# Sensors.net
KiCad netlist of a schematic drawn in Altium Designer
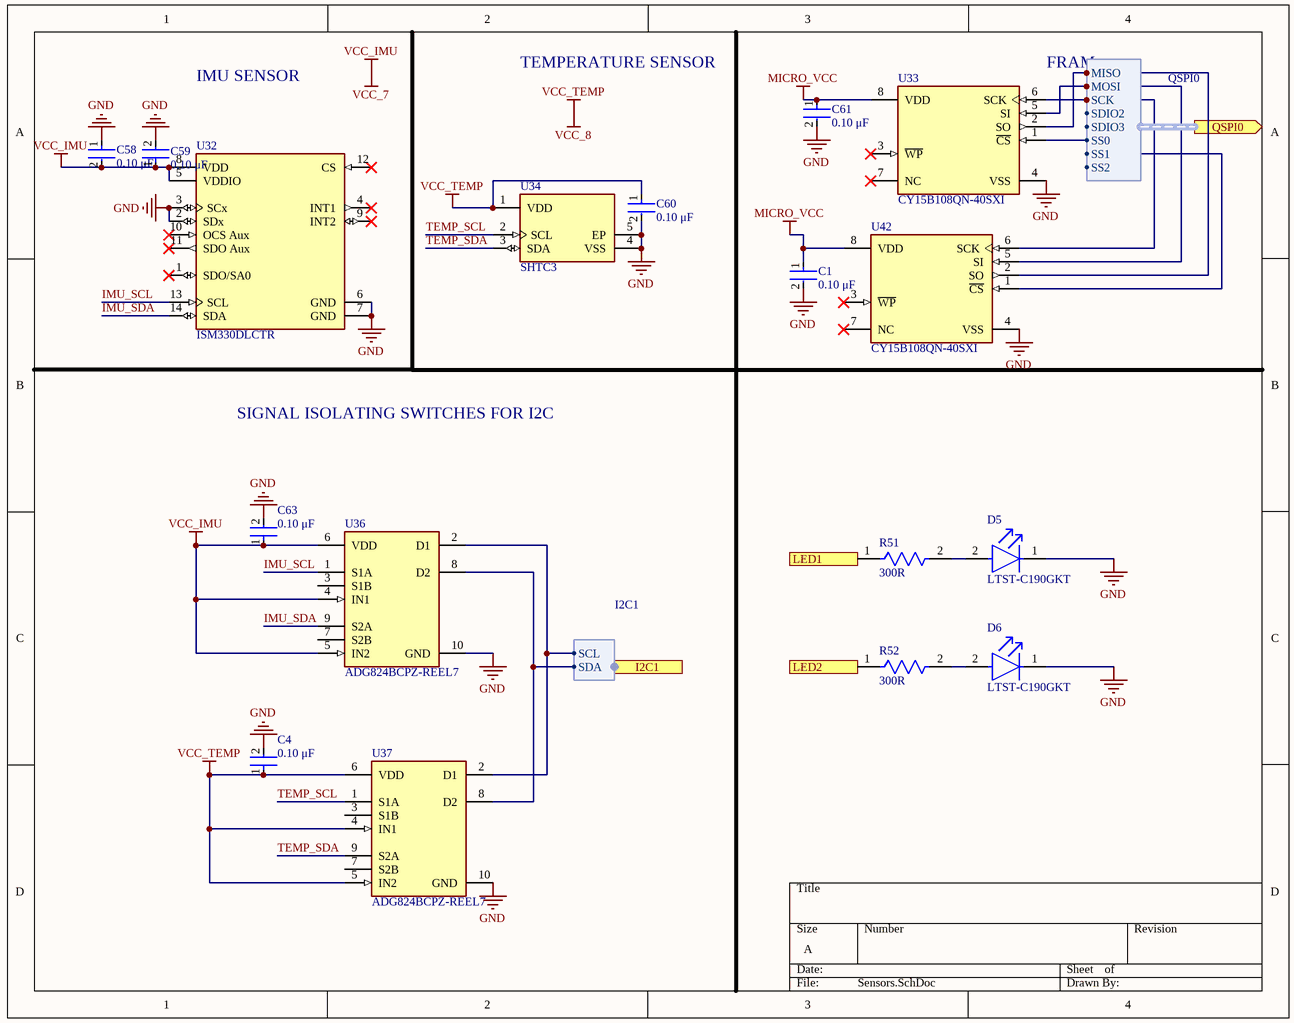
[diagram p0: Sensors.SchDoc]

(export (version "E")
  (design (tool "Eeschema 10.0.6"))
  (components
    (comp (ref "C1")
      (value "C0402C104K8PACTU")
      (footprint "FP-C0402-BB-MFG")
      (description "CAP CER 0.1UF 10V X5R 0402")
      (fields
        (field (name "CAPACITANCE") "0.10 μF")
        (field (name "MANUFACTURER") "Kemet")
        (field (name "TOLERANCE") "0.1")
      )
      (libsource (lib "Altium Content Vault") (part "b4654b650e69147ec39a6b967a45e02"))
    )
    (comp (ref "C4")
      (value "C0402C104K8PACTU")
      (footprint "FP-C0402-BB-MFG")
      (description "CAP CER 0.1UF 10V X5R 0402")
      (fields
        (field (name "CAPACITANCE") "0.10 μF")
        (field (name "MANUFACTURER") "Kemet")
        (field (name "TOLERANCE") "0.1")
      )
      (libsource (lib "Altium Content Vault") (part "b4654b650e69147ec39a6b967a45e02"))
    )
    (comp (ref "C58")
      (value "C0402C104K8PACTU")
      (footprint "FP-C0402-BB-MFG")
      (description "CAP CER 0.1UF 10V X5R 0402")
      (fields
        (field (name "CAPACITANCE") "0.10 μF")
        (field (name "MANUFACTURER") "Kemet")
        (field (name "TOLERANCE") "0.1")
      )
      (libsource (lib "Altium Content Vault") (part "b4654b650e69147ec39a6b967a45e02"))
    )
    (comp (ref "C59")
      (value "C0402C104K8PACTU")
      (footprint "FP-C0402-BB-MFG")
      (description "CAP CER 0.1UF 10V X5R 0402")
      (fields
        (field (name "CAPACITANCE") "0.10 μF")
        (field (name "MANUFACTURER") "Kemet")
        (field (name "TOLERANCE") "0.1")
      )
      (libsource (lib "Altium Content Vault") (part "b4654b650e69147ec39a6b967a45e02"))
    )
    (comp (ref "C60")
      (value "C0402C104K8PACTU")
      (footprint "FP-C0402-BB-MFG")
      (description "CAP CER 0.1UF 10V X5R 0402")
      (fields
        (field (name "CAPACITANCE") "0.10 μF")
        (field (name "MANUFACTURER") "Kemet")
        (field (name "TOLERANCE") "0.1")
      )
      (libsource (lib "Altium Content Vault") (part "b4654b650e69147ec39a6b967a45e02"))
    )
    (comp (ref "C61")
      (value "C0402C104K8PACTU")
      (footprint "FP-C0402-BB-MFG")
      (description "CAP CER 0.1UF 10V X5R 0402")
      (fields
        (field (name "CAPACITANCE") "0.10 μF")
        (field (name "MANUFACTURER") "Kemet")
        (field (name "TOLERANCE") "0.1")
      )
      (libsource (lib "Altium Content Vault") (part "b4654b650e69147ec39a6b967a45e02"))
    )
    (comp (ref "C63")
      (value "C0402C104K8PACTU")
      (footprint "FP-C0402-BB-MFG")
      (description "CAP CER 0.1UF 10V X5R 0402")
      (fields
        (field (name "CAPACITANCE") "0.10 μF")
        (field (name "MANUFACTURER") "Kemet")
        (field (name "TOLERANCE") "0.1")
      )
      (libsource (lib "Altium Content Vault") (part "b4654b650e69147ec39a6b967a45e02"))
    )
    (comp (ref "D5")
      (value "LTST-C190GKT")
      (footprint "FP-LTST-C190GKT-MFG")
      (description "LED GREEN CLEAR CHIP SMD")
      (fields (field (name "VOLTAGE") "2V"))
      (libsource (lib "Altium Content Vault") (part "8706943c75ba83719d021d2fdc84c58"))
    )
    (comp (ref "D6")
      (value "LTST-C190GKT")
      (footprint "FP-LTST-C190GKT-MFG")
      (description "LED GREEN CLEAR CHIP SMD")
      (fields (field (name "VOLTAGE") "2V"))
      (libsource (lib "Altium Content Vault") (part "8706943c75ba83719d021d2fdc84c58"))
    )
    (comp (ref "R51")
      (value "CRCW0603300RFKEA")
      (footprint "FP-CRCW0603-e3-IPC_A")
      (description "RES Thick Film, 300Ω, 1%, 0.1W, 100ppm/°C, 0603")
      (fields (field (name "TOLERANCE") "1%") (field (name "RESISTANCE") "300R"))
      (libsource (lib "Altium Content Vault") (part "1029c3af85768c4190bb7ad29bc67b5"))
    )
    (comp (ref "R52")
      (value "CRCW0603300RFKEA")
      (footprint "FP-CRCW0603-e3-IPC_A")
      (description "RES Thick Film, 300Ω, 1%, 0.1W, 100ppm/°C, 0603")
      (fields (field (name "TOLERANCE") "1%") (field (name "RESISTANCE") "300R"))
      (libsource (lib "Altium Content Vault") (part "1029c3af85768c4190bb7ad29bc67b5"))
    )
    (comp (ref "U32")
      (value "ISM330DLCTR")
      (footprint "FP-LGA-14L-DM00249496-MFG")
      (description "INEMO INERTIAL MODULE")
      (fields
        (field (name "MANUFACTURER") "STMicroelectronics")
        (field (name "OCTOPART") "https://octopart.com/ism330dlctr-stmicroelectronics-85149243")
      )
      (libsource (lib "Altium Content Vault") (part "7cb83b91da826bd22f6a735c633f5ac"))
    )
    (comp (ref "U33")
      (value "CY15B108QN-40SXI")
      (footprint "FP-001-85261-IPC_C")
      (description "IC FRAM 8MBIT 40MHZ 8EIAJ")
      (libsource (lib "Altium Content Vault") (part "94cc5f17500dd1907c0ebdcd3efa3d4"))
    )
    (comp (ref "U34")
      (value "SHTC3")
      (footprint "FP-SHTC3-MFG")
      (description "SENSOR HUMI/TEMP I2C 2% SMD")
      (fields
        (field (name "MANUFACTURER") "Sensirion")
        (field (name "OCTOPART") "https://octopart.com/shtc3-sensirion-91912225")
      )
      (libsource (lib "Altium Content Vault") (part "92e21da4ceb1e434b50171ab113565b"))
    )
    (comp (ref "U36")
      (value "ADG824BCPZ-REEL7")
      (footprint "FP-CP-10-10-MFG")
      (description "IC SWITCH DUAL SPDT 10LFCSP")
      (fields
        (field (name "OCTOPART") "https://octopart.com/adg824bcpz-reel7-analog+devices-12410880")
        (field (name "MANUFACTURER") "Analog Devices")
      )
      (libsource (lib "Altium Content Vault") (part "750f7653eda72c1ba3820f182f788e1"))
    )
    (comp (ref "U37")
      (value "ADG824BCPZ-REEL7")
      (footprint "FP-CP-10-10-MFG")
      (description "IC SWITCH DUAL SPDT 10LFCSP")
      (fields
        (field (name "OCTOPART") "https://octopart.com/adg824bcpz-reel7-analog+devices-12410880")
        (field (name "MANUFACTURER") "Analog Devices")
      )
      (libsource (lib "Altium Content Vault") (part "750f7653eda72c1ba3820f182f788e1"))
    )
    (comp (ref "U42")
      (value "CY15B108QN-40SXI")
      (footprint "FP-001-85261-IPC_C")
      (description "IC FRAM 8MBIT 40MHZ 8EIAJ")
      (libsource (lib "Altium Content Vault") (part "94cc5f17500dd1907c0ebdcd3efa3d4"))
    )
  )
  (nets
    (net (code "3") (name "/IMU_SCL") (class "Default")
      (node (ref "U32") (pin "13") (pinfunction "SCL_13") (pintype "input"))
      (node (ref "U36") (pin "1") (pinfunction "S1A_1") (pintype "passive"))
    )
    (net (code "4") (name "/IMU_SDA") (class "Default")
      (node (ref "U32") (pin "14") (pinfunction "SDA_14") (pintype "bidirectional"))
      (node (ref "U36") (pin "9") (pinfunction "S2A_9") (pintype "passive"))
    )
    (net (code "5") (name "/LED1") (class "Default")
      (node (ref "R51") (pin "1") (pinfunction "1_1") (pintype "passive"))
    )
    (net (code "6") (name "/LED2") (class "Default")
      (node (ref "R52") (pin "1") (pinfunction "1_1") (pintype "passive"))
    )
    (net (code "7") (name "/MISO") (class "Default")
      (node (ref "U33") (pin "2") (pinfunction "SO_2") (pintype "output"))
      (node (ref "U42") (pin "2") (pinfunction "SO_2") (pintype "output"))
    )
    (net (code "8") (name "/MOSI") (class "Default")
      (node (ref "U33") (pin "5") (pinfunction "SI_5") (pintype "input"))
      (node (ref "U42") (pin "5") (pinfunction "SI_5") (pintype "input"))
    )
    (net (code "9") (name "/SCK") (class "Default")
      (node (ref "U33") (pin "6") (pinfunction "SCK_6") (pintype "input"))
      (node (ref "U42") (pin "6") (pinfunction "SCK_6") (pintype "input"))
    )
    (net (code "10") (name "/SCL") (class "Default")
      (node (ref "U36") (pin "2") (pinfunction "D1_2") (pintype "passive"))
      (node (ref "U37") (pin "2") (pinfunction "D1_2") (pintype "passive"))
    )
    (net (code "11") (name "/SDA") (class "Default")
      (node (ref "U36") (pin "8") (pinfunction "D2_8") (pintype "passive"))
      (node (ref "U37") (pin "8") (pinfunction "D2_8") (pintype "passive"))
    )
    (net (code "12") (name "/SS0") (class "Default")
      (node (ref "U33") (pin "1") (pinfunction "~{CS}_1") (pintype "input"))
    )
    (net (code "13") (name "/SS1") (class "Default")
      (node (ref "U42") (pin "1") (pinfunction "~{CS}_1") (pintype "input"))
    )
    (net (code "14") (name "/TEMP_SCL") (class "Default")
      (node (ref "U34") (pin "2") (pinfunction "SCL_2") (pintype "input"))
      (node (ref "U37") (pin "1") (pinfunction "S1A_1") (pintype "passive"))
    )
    (net (code "15") (name "/TEMP_SDA") (class "Default")
      (node (ref "U34") (pin "3") (pinfunction "SDA_3") (pintype "bidirectional"))
      (node (ref "U37") (pin "9") (pinfunction "S2A_9") (pintype "passive"))
    )
    (net (code "18") (name "GND") (class "Default")
      (node (ref "C1") (pin "2") (pinfunction "2_2") (pintype "passive"))
      (node (ref "C4") (pin "2") (pinfunction "2_2") (pintype "passive"))
      (node (ref "C58") (pin "1") (pinfunction "1_1") (pintype "passive"))
      (node (ref "C59") (pin "2") (pinfunction "2_2") (pintype "passive"))
      (node (ref "C60") (pin "2") (pinfunction "2_2") (pintype "passive"))
      (node (ref "C61") (pin "2") (pinfunction "2_2") (pintype "passive"))
      (node (ref "C63") (pin "2") (pinfunction "2_2") (pintype "passive"))
      (node (ref "D5") (pin "1") (pinfunction "C_1") (pintype "passive"))
      (node (ref "D6") (pin "1") (pinfunction "C_1") (pintype "passive"))
      (node (ref "U32") (pin "2") (pinfunction "SDx_2") (pintype "bidirectional"))
      (node (ref "U32") (pin "3") (pinfunction "SCx_3") (pintype "bidirectional"))
      (node (ref "U32") (pin "6") (pinfunction "GND_6") (pintype "power_in"))
      (node (ref "U32") (pin "7") (pinfunction "GND_7") (pintype "power_in"))
      (node (ref "U33") (pin "4") (pinfunction "VSS_4") (pintype "power_in"))
      (node (ref "U34") (pin "4") (pinfunction "VSS_4") (pintype "power_in"))
      (node (ref "U34") (pin "5") (pinfunction "EP_5") (pintype "power_in"))
      (node (ref "U36") (pin "10") (pinfunction "GND_10") (pintype "power_in"))
      (node (ref "U37") (pin "10") (pinfunction "GND_10") (pintype "power_in"))
      (node (ref "U42") (pin "4") (pinfunction "VSS_4") (pintype "power_in"))
    )
    (net (code "19") (name "MICRO_VCC") (class "Default")
      (node (ref "C1") (pin "1") (pinfunction "1_1") (pintype "passive"))
      (node (ref "C61") (pin "1") (pinfunction "1_1") (pintype "passive"))
      (node (ref "U33") (pin "8") (pinfunction "VDD_8") (pintype "power_in"))
      (node (ref "U42") (pin "8") (pinfunction "VDD_8") (pintype "power_in"))
    )
    (net (code "20") (name "Net-(D5-A)") (class "Default")
      (node (ref "D5") (pin "2") (pinfunction "A_2") (pintype "passive"))
      (node (ref "R51") (pin "2") (pinfunction "2_2") (pintype "passive"))
    )
    (net (code "21") (name "Net-(D6-A)") (class "Default")
      (node (ref "D6") (pin "2") (pinfunction "A_2") (pintype "passive"))
      (node (ref "R52") (pin "2") (pinfunction "2_2") (pintype "passive"))
    )
    (net (code "22") (name "VCC_7") (class "Default")
      (node (ref "C58") (pin "2") (pinfunction "2_2") (pintype "passive"))
      (node (ref "C59") (pin "1") (pinfunction "1_1") (pintype "passive"))
      (node (ref "C63") (pin "1") (pinfunction "1_1") (pintype "passive"))
      (node (ref "U32") (pin "5") (pinfunction "VDDIO_5") (pintype "power_in"))
      (node (ref "U32") (pin "8") (pinfunction "VDD_8") (pintype "power_in"))
      (node (ref "U36") (pin "4") (pinfunction "IN1_4") (pintype "input"))
      (node (ref "U36") (pin "5") (pinfunction "IN2_5") (pintype "input"))
      (node (ref "U36") (pin "6") (pinfunction "VDD_6") (pintype "power_in"))
    )
    (net (code "23") (name "VCC_8") (class "Default")
      (node (ref "C4") (pin "1") (pinfunction "1_1") (pintype "passive"))
      (node (ref "C60") (pin "1") (pinfunction "1_1") (pintype "passive"))
      (node (ref "U34") (pin "1") (pinfunction "VDD_1") (pintype "power_in"))
      (node (ref "U37") (pin "4") (pinfunction "IN1_4") (pintype "input"))
      (node (ref "U37") (pin "5") (pinfunction "IN2_5") (pintype "input"))
      (node (ref "U37") (pin "6") (pinfunction "VDD_6") (pintype "power_in"))
    )
    (net (code "24") (name "unconnected-(U32-CS-Pad12)") (class "Default")
      (node (ref "U32") (pin "12") (pinfunction "CS_12") (pintype "input+no_connect"))
    )
    (net (code "25") (name "unconnected-(U32-INT1-Pad4)") (class "Default")
      (node (ref "U32") (pin "4") (pinfunction "INT1_4") (pintype "output+no_connect"))
    )
    (net (code "26") (name "unconnected-(U32-INT2-Pad9)") (class "Default")
      (node (ref "U32") (pin "9") (pinfunction "INT2_9") (pintype "bidirectional+no_connect"))
    )
    (net (code "27") (name "unconnected-(U32-OCS_Aux-Pad10)") (class "Default")
      (node (ref "U32") (pin "10") (pinfunction "OCS_Aux_10") (pintype "input+no_connect"))
    )
    (net (code "28") (name "unconnected-(U32-SDO_Aux-Pad11)") (class "Default")
      (node (ref "U32") (pin "11") (pinfunction "SDO_Aux_11") (pintype "output+no_connect"))
    )
    (net (code "29") (name "unconnected-(U32-SDO{slash}SA0-Pad1)") (class "Default")
      (node (ref "U32") (pin "1") (pinfunction "SDO/SA0_1") (pintype "bidirectional+no_connect"))
    )
    (net (code "30") (name "unconnected-(U33-NC-Pad7)") (class "Default")
      (node (ref "U33") (pin "7") (pinfunction "NC_7") (pintype "passive+no_connect"))
    )
    (net (code "31") (name "unconnected-(U33-~{WP}-Pad3)") (class "Default")
      (node (ref "U33") (pin "3") (pinfunction "~{WP}_3") (pintype "input+no_connect"))
    )
    (net (code "32") (name "unconnected-(U36-S1B-Pad3)") (class "Default")
      (node (ref "U36") (pin "3") (pinfunction "S1B_3") (pintype "passive"))
    )
    (net (code "33") (name "unconnected-(U36-S2B-Pad7)") (class "Default")
      (node (ref "U36") (pin "7") (pinfunction "S2B_7") (pintype "passive"))
    )
    (net (code "34") (name "unconnected-(U37-S1B-Pad3)") (class "Default")
      (node (ref "U37") (pin "3") (pinfunction "S1B_3") (pintype "passive"))
    )
    (net (code "35") (name "unconnected-(U37-S2B-Pad7)") (class "Default")
      (node (ref "U37") (pin "7") (pinfunction "S2B_7") (pintype "passive"))
    )
    (net (code "36") (name "unconnected-(U42-NC-Pad7)") (class "Default")
      (node (ref "U42") (pin "7") (pinfunction "NC_7") (pintype "passive+no_connect"))
    )
    (net (code "37") (name "unconnected-(U42-~{WP}-Pad3)") (class "Default")
      (node (ref "U42") (pin "3") (pinfunction "~{WP}_3") (pintype "input+no_connect"))
    )
  )
)
